# music.net
KiCad netlist of a schematic drawn in EAGLE
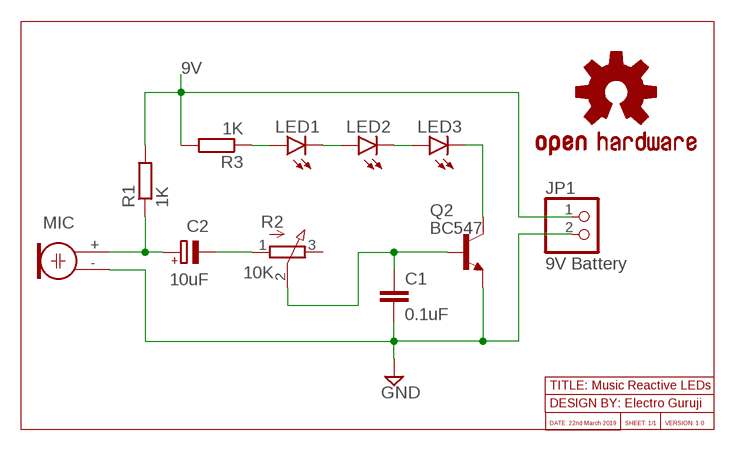
[diagram p0: schematic, sheet 1]

(export (version "E")
  (design (tool "Eeschema 10.0.6"))
  (components
    (comp (ref "C1")
      (value "0.1uF")
      (footprint "eagle-import:C025-050X050")
      (libsource (lib "eagle-import") (part "C-EU025-050X050"))
    )
    (comp (ref "C2")
      (value "10uF")
      (footprint "eagle-import:E2,5-6")
      (libsource (lib "eagle-import") (part "CPOL-EUE2.5-6"))
    )
    (comp (ref "JP1")
      (value "9V Battery")
      (footprint "eagle-import:1X02")
      (libsource (lib "eagle-import") (part "PINHD-1X2"))
    )
    (comp (ref "LED1")
      (value "LED5MM")
      (footprint "eagle-import:LED5MM")
      (libsource (lib "eagle-import") (part "LED5MM"))
    )
    (comp (ref "LED2")
      (value "LED5MM")
      (footprint "eagle-import:LED5MM")
      (libsource (lib "eagle-import") (part "LED5MM"))
    )
    (comp (ref "LED3")
      (value "LED5MM")
      (footprint "eagle-import:LED5MM")
      (libsource (lib "eagle-import") (part "LED5MM"))
    )
    (comp (ref "LOGO1")
      (value "OSHW-LOGOMINI")
      (footprint "eagle-import:OSHW-LOGO-MINI")
      (libsource (lib "eagle-import") (part "OSHW-LOGOMINI"))
    )
    (comp (ref "MIC")
      (value "ELECTRET")
      (footprint "eagle-import:9.7ELECTRET")
      (libsource (lib "eagle-import") (part "ELECTRET"))
    )
    (comp (ref "Q2")
      (value "BC547")
      (footprint "eagle-import:TO92-CBE")
      (libsource (lib "eagle-import") (part "-NPN-TO92-CBE"))
    )
    (comp (ref "R1")
      (value "1K")
      (footprint "eagle-import:0207_10")
      (libsource (lib "eagle-import") (part "R-EU_0207/10"))
    )
    (comp (ref "R2")
      (value "10K")
      (footprint "eagle-import:3RP_1610N")
      (libsource (lib "eagle-import") (part "3RP/1610N"))
    )
    (comp (ref "R3")
      (value "1K")
      (footprint "eagle-import:0207_10")
      (libsource (lib "eagle-import") (part "R-EU_0207/10"))
    )
  )
  (nets
    (net (code "1") (name "/9V") (class "Default")
      (node (ref "JP1") (pin "1") (pinfunction "1_1") (pintype "passive"))
      (node (ref "R1") (pin "2") (pinfunction "2_2") (pintype "passive"))
      (node (ref "R3") (pin "2") (pinfunction "2_2") (pintype "passive"))
    )
    (net (code "2") (name "GND") (class "Default")
      (node (ref "C1") (pin "2") (pinfunction "2_2") (pintype "passive"))
      (node (ref "JP1") (pin "2") (pinfunction "2_2") (pintype "passive"))
      (node (ref "MIC") (pin "-") (pinfunction "1_-") (pintype "passive"))
      (node (ref "Q2") (pin "E") (pinfunction "E_E") (pintype "passive"))
    )
    (net (code "3") (name "Net-(LED1-C)") (class "Default")
      (node (ref "LED1") (pin "K") (pinfunction "C_K") (pintype "passive"))
      (node (ref "LED2") (pin "A") (pinfunction "A_A") (pintype "passive"))
    )
    (net (code "4") (name "Net-(LED1-PadA)") (class "Default")
      (node (ref "LED1") (pin "A") (pinfunction "A_A") (pintype "passive"))
      (node (ref "R3") (pin "1") (pinfunction "1_1") (pintype "passive"))
    )
    (net (code "5") (name "Net-(LED2-C)") (class "Default")
      (node (ref "LED2") (pin "K") (pinfunction "C_K") (pintype "passive"))
      (node (ref "LED3") (pin "A") (pinfunction "A_A") (pintype "passive"))
    )
    (net (code "6") (name "Net-(LED3-C)") (class "Default")
      (node (ref "LED3") (pin "K") (pinfunction "C_K") (pintype "passive"))
      (node (ref "Q2") (pin "C") (pinfunction "C_C") (pintype "passive"))
    )
    (net (code "7") (name "Net-(MIC-2)") (class "Default")
      (node (ref "C2") (pin "+") (pinfunction "+_+") (pintype "passive"))
      (node (ref "MIC") (pin "+") (pinfunction "2_+") (pintype "passive"))
      (node (ref "R1") (pin "1") (pinfunction "1_1") (pintype "passive"))
    )
    (net (code "8") (name "Net-(R2-A)") (class "Default")
      (node (ref "C2") (pin "-") (pinfunction "-_-") (pintype "passive"))
      (node (ref "R2") (pin "1") (pinfunction "A_1") (pintype "passive"))
    )
    (net (code "9") (name "Net-(R2-S)") (class "Default")
      (node (ref "C1") (pin "1") (pinfunction "1_1") (pintype "passive"))
      (node (ref "Q2") (pin "B") (pinfunction "B_B") (pintype "passive"))
      (node (ref "R2") (pin "2") (pinfunction "S_2") (pintype "passive"))
    )
    (net (code "10") (name "unconnected-(R2-E-Pad3)") (class "Default")
      (node (ref "R2") (pin "3") (pinfunction "E_3") (pintype "passive"))
    )
  )
)
